# top_power.net
KiCad netlist of a schematic drawn in Altium Designer
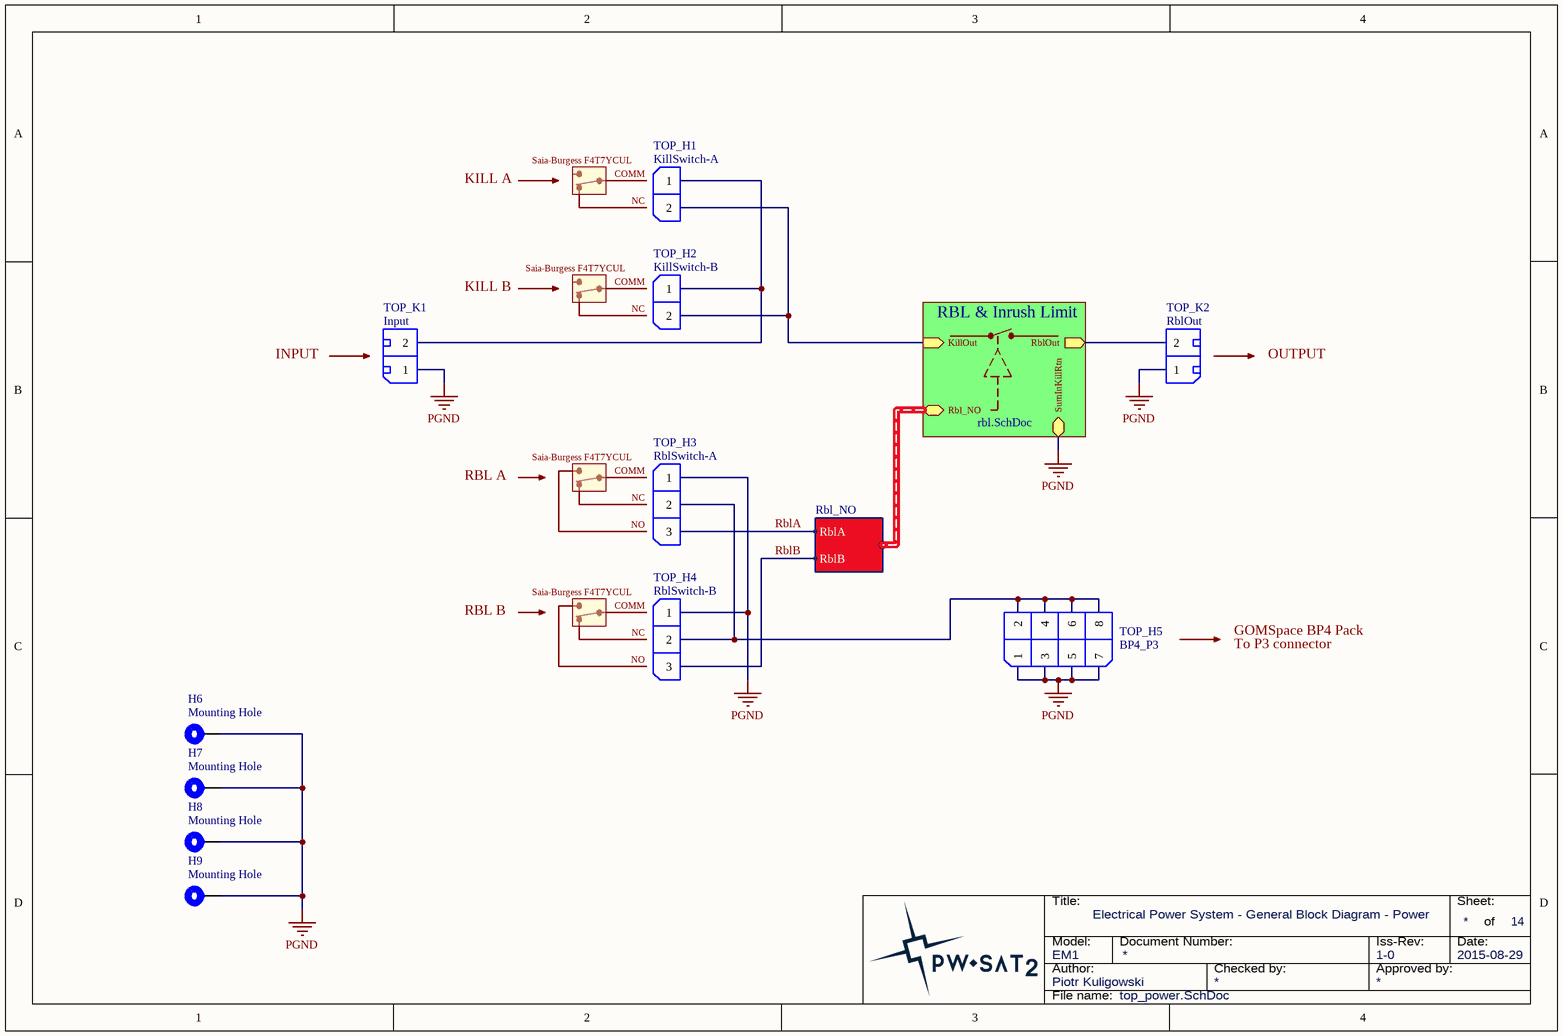
[diagram p0: top_power.SchDoc]

(export (version "E")
  (design (tool "Eeschema 10.0.6"))
  (components
    (comp (ref "H6")
      (value "Mounting Hole")
      (footprint "PC-104_PcbMntHole_M3")
      (description "PCB Mounting Hole")
      (libsource (lib "connectors_printed-circuit-board") (part "MntHole"))
    )
    (comp (ref "H7")
      (value "Mounting Hole")
      (footprint "PC-104_PcbMntHole_M3")
      (description "PCB Mounting Hole")
      (libsource (lib "connectors_printed-circuit-board") (part "MntHole"))
    )
    (comp (ref "H8")
      (value "Mounting Hole")
      (footprint "PC-104_PcbMntHole_M3")
      (description "PCB Mounting Hole")
      (libsource (lib "connectors_printed-circuit-board") (part "MntHole"))
    )
    (comp (ref "H9")
      (value "Mounting Hole")
      (footprint "PC-104_PcbMntHole_M3")
      (description "PCB Mounting Hole")
      (libsource (lib "connectors_printed-circuit-board") (part "MntHole"))
    )
    (comp (ref "TOP_H1")
      (value "KillSwitch-A")
      (footprint "Harwin_Datamate_L-Tek_M80-8760205")
      (description "Harwin DataMate L-Tek, 2mm pitch, 1x2pin.")
      (libsource (lib "connectors_printed-circuit-board") (part "Harwin_Datamate_L-Tek_1x2pin"))
    )
    (comp (ref "TOP_H2")
      (value "KillSwitch-B")
      (footprint "Harwin_Datamate_L-Tek_M80-8760205")
      (description "Harwin DataMate L-Tek, 2mm pitch, 1x2pin.")
      (libsource (lib "connectors_printed-circuit-board") (part "Harwin_Datamate_L-Tek_1x2pin"))
    )
    (comp (ref "TOP_H3")
      (value "RblSwitch-A")
      (footprint "Harwin_Datamate_L-Tek_M80-8770305")
      (description "Harwin DataMate L-Tek, 2mm pitch, 1x3pin.")
      (libsource (lib "connectors_printed-circuit-board") (part "Harwin_Datamate_L-Tek_1x3pin"))
    )
    (comp (ref "TOP_H4")
      (value "RblSwitch-B")
      (footprint "Harwin_Datamate_L-Tek_M80-8770305")
      (description "Harwin DataMate L-Tek, 2mm pitch, 1x3pin.")
      (libsource (lib "connectors_printed-circuit-board") (part "Harwin_Datamate_L-Tek_1x3pin"))
    )
    (comp (ref "TOP_H5")
      (value "BP4_P3")
      (footprint "Harwin_Datamate_L-Tek_M80-8670805")
      (description "Harwin DataMate L-Tek, 2mm pitch, 2x4pin.")
      (libsource (lib "connectors_printed-circuit-board") (part "Harwin_Datamate_L-Tek_2x4pin"))
    )
    (comp (ref "TOP_K1")
      (value "TB-2.5-PD-xx")
      (footprint "TerminalBlock_Spring_2.54_2-R")
      (description "Terminal block with spring, 2-pin, 2.54mm pitch, right angle.")
      (fields (field (name "PROVIDERPARTNUMBER") "Input") (field (name "PROVIDER") "TME.eu"))
      (libsource (lib "connectors_printed-circuit-board") (part "TerminalBlock_Spring_2.54_2-R"))
    )
    (comp (ref "TOP_K2")
      (value "TB-2.5-PD-xx")
      (footprint "TerminalBlock_Spring_2.54_2-R")
      (description "Terminal block with spring, 2-pin, 2.54mm pitch, right angle.")
      (fields (field (name "PROVIDERPARTNUMBER") "RblOut") (field (name "PROVIDER") "TME.eu"))
      (libsource (lib "connectors_printed-circuit-board") (part "TerminalBlock_Spring_2.54_2-R"))
    )
  )
  (nets
    (net (code "2") (name "/KillOut") (class "Default")
      (node (ref "TOP_H1") (pin "2") (pinfunction "2_2") (pintype "passive"))
      (node (ref "TOP_H2") (pin "2") (pinfunction "2_2") (pintype "passive"))
    )
    (net (code "3") (name "/RblA") (class "Default")
      (node (ref "TOP_H3") (pin "3") (pinfunction "3_3") (pintype "passive"))
    )
    (net (code "4") (name "/RblB") (class "Default")
      (node (ref "TOP_H4") (pin "3") (pinfunction "3_3") (pintype "passive"))
    )
    (net (code "5") (name "/RblOut") (class "Default")
      (node (ref "TOP_K2") (pin "2") (pinfunction "2_2") (pintype "passive"))
    )
    (net (code "7") (name "Net-(TOP_H1-Pad1)") (class "Default")
      (node (ref "TOP_H1") (pin "1") (pinfunction "1_1") (pintype "passive"))
      (node (ref "TOP_H2") (pin "1") (pinfunction "1_1") (pintype "passive"))
      (node (ref "TOP_K1") (pin "2") (pinfunction "2_2") (pintype "passive"))
    )
    (net (code "8") (name "Net-(TOP_H3-Pad2)") (class "Default")
      (node (ref "TOP_H3") (pin "2") (pinfunction "2_2") (pintype "passive"))
      (node (ref "TOP_H4") (pin "2") (pinfunction "2_2") (pintype "passive"))
      (node (ref "TOP_H5") (pin "2") (pinfunction "2_2") (pintype "passive"))
      (node (ref "TOP_H5") (pin "4") (pinfunction "4_4") (pintype "passive"))
      (node (ref "TOP_H5") (pin "6") (pinfunction "6_6") (pintype "passive"))
      (node (ref "TOP_H5") (pin "8") (pinfunction "8_8") (pintype "passive"))
    )
    (net (code "9") (name "PGND") (class "Default")
      (node (ref "H6") (pin "1") (pinfunction "1_1") (pintype "passive"))
      (node (ref "H7") (pin "1") (pinfunction "1_1") (pintype "passive"))
      (node (ref "H8") (pin "1") (pinfunction "1_1") (pintype "passive"))
      (node (ref "H9") (pin "1") (pinfunction "1_1") (pintype "passive"))
      (node (ref "TOP_H3") (pin "1") (pinfunction "1_1") (pintype "passive"))
      (node (ref "TOP_H4") (pin "1") (pinfunction "1_1") (pintype "passive"))
      (node (ref "TOP_H5") (pin "1") (pinfunction "1_1") (pintype "passive"))
      (node (ref "TOP_H5") (pin "3") (pinfunction "3_3") (pintype "passive"))
      (node (ref "TOP_H5") (pin "5") (pinfunction "5_5") (pintype "passive"))
      (node (ref "TOP_H5") (pin "7") (pinfunction "7_7") (pintype "passive"))
      (node (ref "TOP_K1") (pin "1") (pinfunction "1_1") (pintype "passive"))
      (node (ref "TOP_K2") (pin "1") (pinfunction "1_1") (pintype "passive"))
    )
  )
)
